# SchemaFin.net
KiCad netlist of a schematic drawn in EAGLE
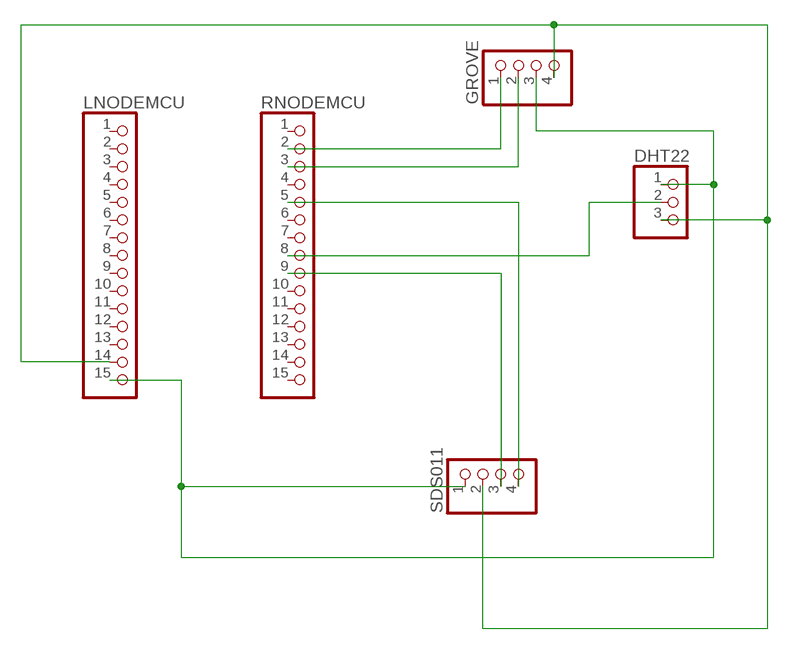
[diagram p0: schematic, sheet 1]

(export (version "E")
  (design (tool "Eeschema 10.0.6"))
  (components
    (comp (ref "DHT22")
      (value "PINHD-1X3")
      (footprint "eagle-import:1X03")
      (libsource (lib "eagle-import") (part "PINHD-1X3"))
    )
    (comp (ref "GROVE")
      (value "PINHD-1X4M")
      (footprint "eagle-import:1X04M")
      (libsource (lib "eagle-import") (part "PINHD-1X4M"))
    )
    (comp (ref "LNODEMCU")
      (value "PINHD-1X15")
      (footprint "eagle-import:1X15")
      (libsource (lib "eagle-import") (part "PINHD-1X15"))
    )
    (comp (ref "RNODEMCU")
      (value "PINHD-1X15")
      (footprint "eagle-import:1X15")
      (libsource (lib "eagle-import") (part "PINHD-1X15"))
    )
    (comp (ref "SDS011")
      (value "PINHD-1X4")
      (footprint "eagle-import:1X04")
      (libsource (lib "eagle-import") (part "pinhead_325_PINHD-1X4"))
    )
  )
  (nets
    (net (code "1") (name "Net-(DHT22-Pad1)") (class "Default")
      (node (ref "DHT22") (pin "1") (pinfunction "1_1") (pintype "passive"))
      (node (ref "GROVE") (pin "3") (pinfunction "3_3") (pintype "passive"))
      (node (ref "LNODEMCU") (pin "15") (pinfunction "15_15") (pintype "passive"))
      (node (ref "SDS011") (pin "1") (pinfunction "1_1") (pintype "passive"))
    )
    (net (code "2") (name "Net-(DHT22-Pad2)") (class "Default")
      (node (ref "DHT22") (pin "2") (pinfunction "2_2") (pintype "passive"))
      (node (ref "RNODEMCU") (pin "8") (pinfunction "8_8") (pintype "passive"))
    )
    (net (code "3") (name "Net-(DHT22-Pad3)") (class "Default")
      (node (ref "DHT22") (pin "3") (pinfunction "3_3") (pintype "passive"))
      (node (ref "GROVE") (pin "4") (pinfunction "4_4") (pintype "passive"))
      (node (ref "LNODEMCU") (pin "14") (pinfunction "14_14") (pintype "passive"))
      (node (ref "SDS011") (pin "2") (pinfunction "2_2") (pintype "passive"))
    )
    (net (code "4") (name "Net-(GROVE-Pad1)") (class "Default")
      (node (ref "GROVE") (pin "1") (pinfunction "1_1") (pintype "passive"))
      (node (ref "RNODEMCU") (pin "2") (pinfunction "2_2") (pintype "passive"))
    )
    (net (code "5") (name "Net-(GROVE-Pad2)") (class "Default")
      (node (ref "GROVE") (pin "2") (pinfunction "2_2") (pintype "passive"))
      (node (ref "RNODEMCU") (pin "3") (pinfunction "3_3") (pintype "passive"))
    )
    (net (code "6") (name "Net-(RNODEMCU-Pad5)") (class "Default")
      (node (ref "RNODEMCU") (pin "5") (pinfunction "5_5") (pintype "passive"))
      (node (ref "SDS011") (pin "4") (pinfunction "4_4") (pintype "passive"))
    )
    (net (code "7") (name "Net-(RNODEMCU-Pad9)") (class "Default")
      (node (ref "RNODEMCU") (pin "9") (pinfunction "9_9") (pintype "passive"))
      (node (ref "SDS011") (pin "3") (pinfunction "3_3") (pintype "passive"))
    )
    (net (code "8") (name "unconnected-(LNODEMCU-Pad1)") (class "Default")
      (node (ref "LNODEMCU") (pin "1") (pinfunction "1_1") (pintype "passive"))
    )
    (net (code "9") (name "unconnected-(LNODEMCU-Pad2)") (class "Default")
      (node (ref "LNODEMCU") (pin "2") (pinfunction "2_2") (pintype "passive"))
    )
    (net (code "10") (name "unconnected-(LNODEMCU-Pad3)") (class "Default")
      (node (ref "LNODEMCU") (pin "3") (pinfunction "3_3") (pintype "passive"))
    )
    (net (code "11") (name "unconnected-(LNODEMCU-Pad4)") (class "Default")
      (node (ref "LNODEMCU") (pin "4") (pinfunction "4_4") (pintype "passive"))
    )
    (net (code "12") (name "unconnected-(LNODEMCU-Pad5)") (class "Default")
      (node (ref "LNODEMCU") (pin "5") (pinfunction "5_5") (pintype "passive"))
    )
    (net (code "13") (name "unconnected-(LNODEMCU-Pad6)") (class "Default")
      (node (ref "LNODEMCU") (pin "6") (pinfunction "6_6") (pintype "passive"))
    )
    (net (code "14") (name "unconnected-(LNODEMCU-Pad7)") (class "Default")
      (node (ref "LNODEMCU") (pin "7") (pinfunction "7_7") (pintype "passive"))
    )
    (net (code "15") (name "unconnected-(LNODEMCU-Pad8)") (class "Default")
      (node (ref "LNODEMCU") (pin "8") (pinfunction "8_8") (pintype "passive"))
    )
    (net (code "16") (name "unconnected-(LNODEMCU-Pad9)") (class "Default")
      (node (ref "LNODEMCU") (pin "9") (pinfunction "9_9") (pintype "passive"))
    )
    (net (code "17") (name "unconnected-(LNODEMCU-Pad10)") (class "Default")
      (node (ref "LNODEMCU") (pin "10") (pinfunction "10_10") (pintype "passive"))
    )
    (net (code "18") (name "unconnected-(LNODEMCU-Pad11)") (class "Default")
      (node (ref "LNODEMCU") (pin "11") (pinfunction "11_11") (pintype "passive"))
    )
    (net (code "19") (name "unconnected-(LNODEMCU-Pad12)") (class "Default")
      (node (ref "LNODEMCU") (pin "12") (pinfunction "12_12") (pintype "passive"))
    )
    (net (code "20") (name "unconnected-(LNODEMCU-Pad13)") (class "Default")
      (node (ref "LNODEMCU") (pin "13") (pinfunction "13_13") (pintype "passive"))
    )
    (net (code "21") (name "unconnected-(RNODEMCU-Pad1)") (class "Default")
      (node (ref "RNODEMCU") (pin "1") (pinfunction "1_1") (pintype "passive"))
    )
    (net (code "22") (name "unconnected-(RNODEMCU-Pad4)") (class "Default")
      (node (ref "RNODEMCU") (pin "4") (pinfunction "4_4") (pintype "passive"))
    )
    (net (code "23") (name "unconnected-(RNODEMCU-Pad6)") (class "Default")
      (node (ref "RNODEMCU") (pin "6") (pinfunction "6_6") (pintype "passive"))
    )
    (net (code "24") (name "unconnected-(RNODEMCU-Pad7)") (class "Default")
      (node (ref "RNODEMCU") (pin "7") (pinfunction "7_7") (pintype "passive"))
    )
    (net (code "25") (name "unconnected-(RNODEMCU-Pad10)") (class "Default")
      (node (ref "RNODEMCU") (pin "10") (pinfunction "10_10") (pintype "passive"))
    )
    (net (code "26") (name "unconnected-(RNODEMCU-Pad11)") (class "Default")
      (node (ref "RNODEMCU") (pin "11") (pinfunction "11_11") (pintype "passive"))
    )
    (net (code "27") (name "unconnected-(RNODEMCU-Pad12)") (class "Default")
      (node (ref "RNODEMCU") (pin "12") (pinfunction "12_12") (pintype "passive"))
    )
    (net (code "28") (name "unconnected-(RNODEMCU-Pad13)") (class "Default")
      (node (ref "RNODEMCU") (pin "13") (pinfunction "13_13") (pintype "passive"))
    )
    (net (code "29") (name "unconnected-(RNODEMCU-Pad14)") (class "Default")
      (node (ref "RNODEMCU") (pin "14") (pinfunction "14_14") (pintype "passive"))
    )
    (net (code "30") (name "unconnected-(RNODEMCU-Pad15)") (class "Default")
      (node (ref "RNODEMCU") (pin "15") (pinfunction "15_15") (pintype "passive"))
    )
  )
)
